# cam.net
KiCad netlist of a schematic drawn in EAGLE
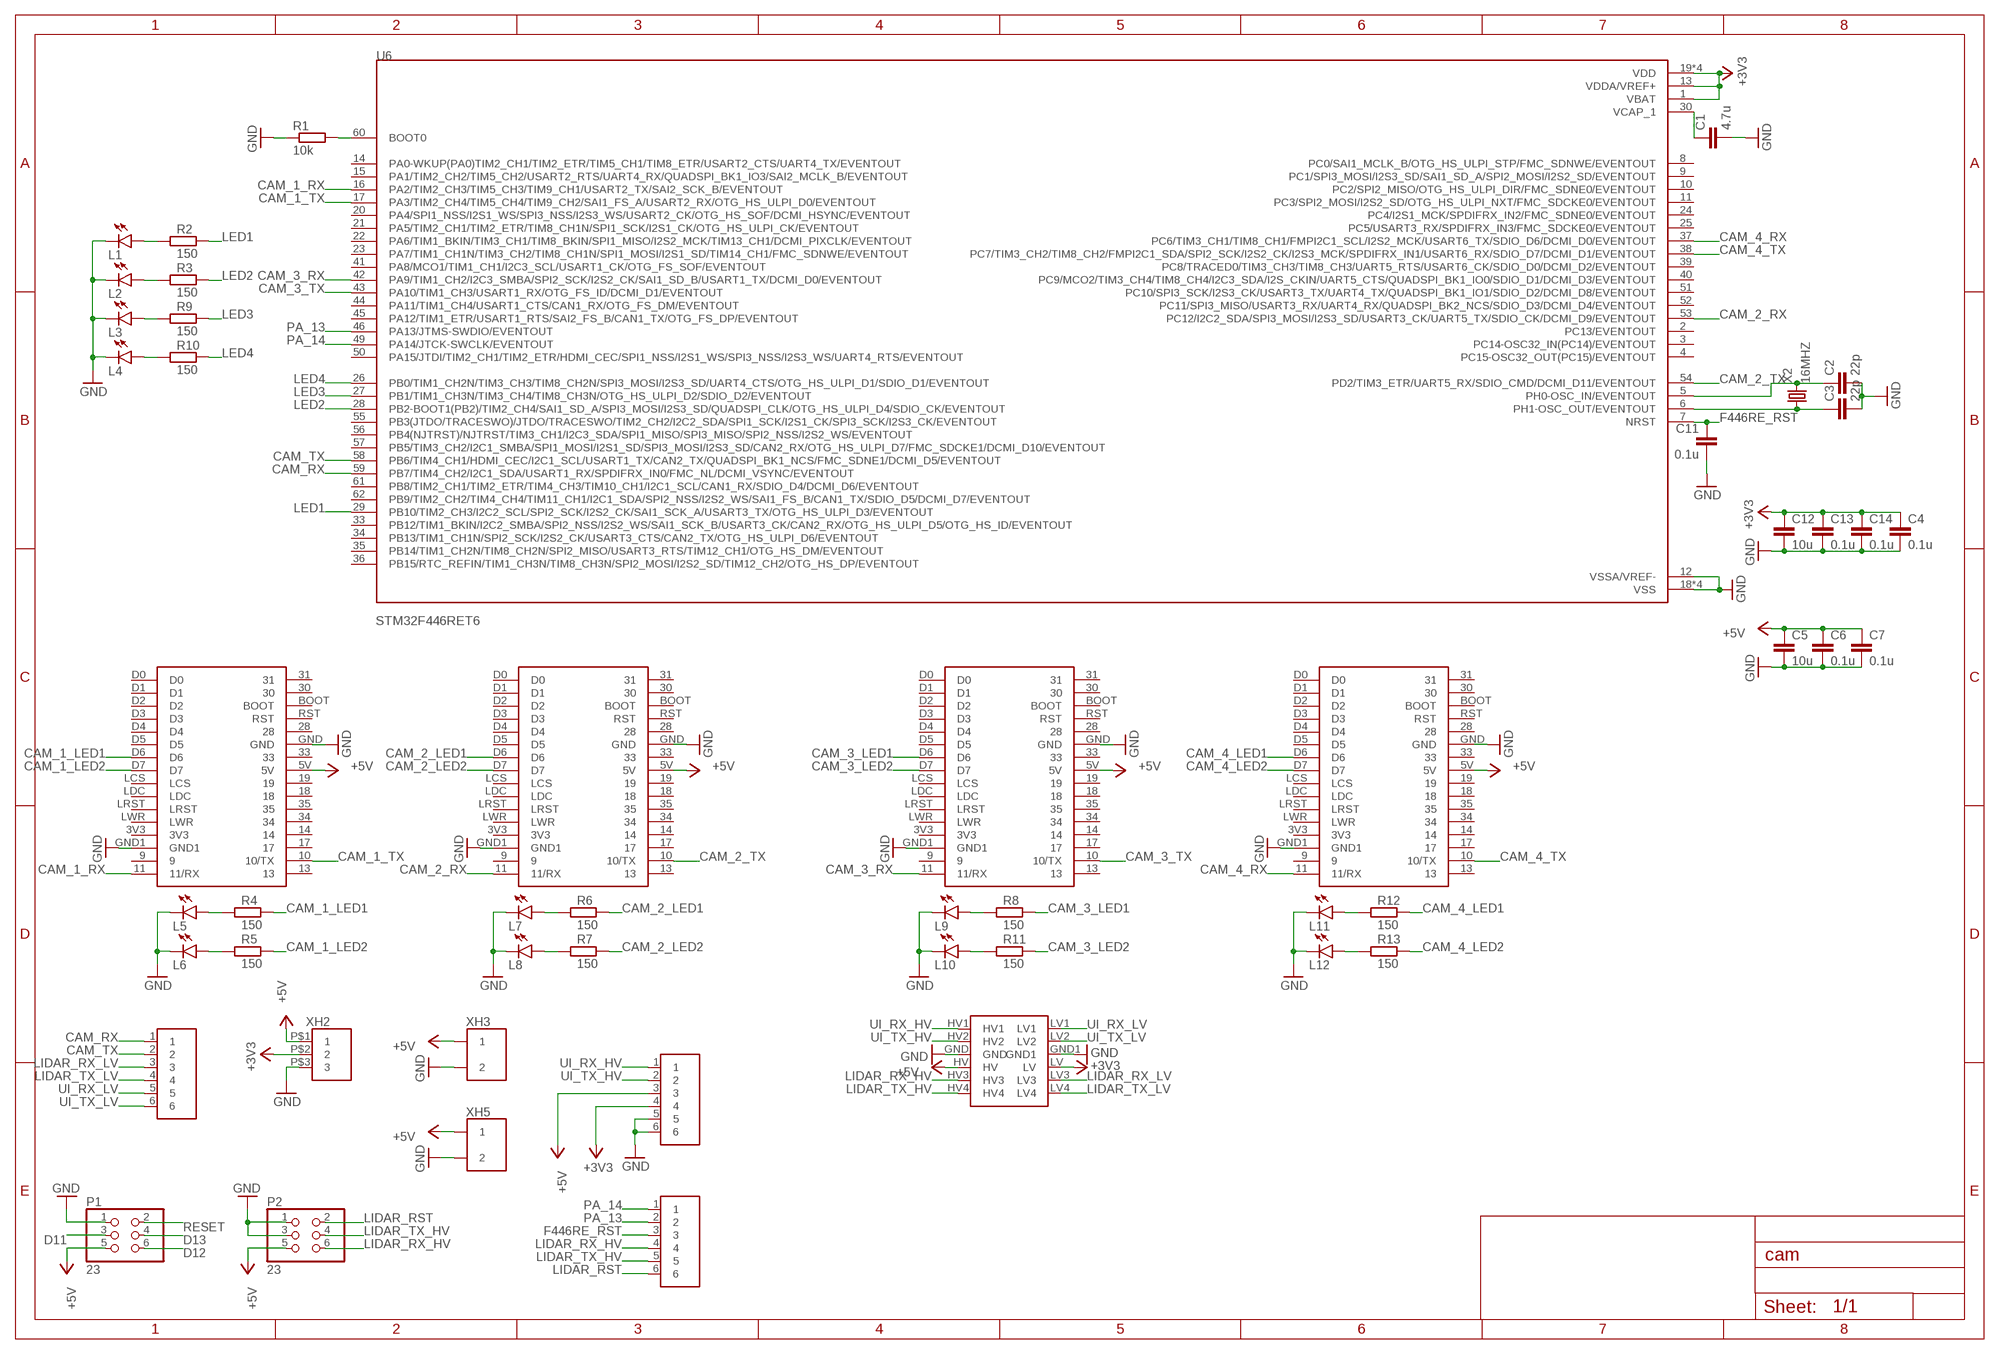
[diagram p0: schematic, sheet 1]

(export (version "E")
  (design (tool "Eeschema 10.0.6"))
  (components
    (comp (ref "C1")
      (value "4.7u")
      (footprint "eagle-import:C0603")
      (libsource (lib "eagle-import") (part "C-EUC0603"))
    )
    (comp (ref "C2")
      (value "22p")
      (footprint "eagle-import:C0603")
      (libsource (lib "eagle-import") (part "C-EUC0603"))
    )
    (comp (ref "C3")
      (value "22p")
      (footprint "eagle-import:C0603")
      (libsource (lib "eagle-import") (part "C-EUC0603"))
    )
    (comp (ref "C4")
      (value "0.1u")
      (footprint "eagle-import:C0603")
      (libsource (lib "eagle-import") (part "C-EUC0603"))
    )
    (comp (ref "C5")
      (value "10u")
      (footprint "eagle-import:C0805")
      (libsource (lib "eagle-import") (part "C-EUC0805"))
    )
    (comp (ref "C6")
      (value "0.1u")
      (footprint "eagle-import:C0603")
      (libsource (lib "eagle-import") (part "C-EUC0603"))
    )
    (comp (ref "C7")
      (value "0.1u")
      (footprint "eagle-import:C0603")
      (libsource (lib "eagle-import") (part "C-EUC0603"))
    )
    (comp (ref "C11")
      (value "0.1u")
      (footprint "eagle-import:C0603")
      (libsource (lib "eagle-import") (part "C-EUC0603"))
    )
    (comp (ref "C12")
      (value "10u")
      (footprint "eagle-import:C0805")
      (libsource (lib "eagle-import") (part "C-EUC0805"))
    )
    (comp (ref "C13")
      (value "0.1u")
      (footprint "eagle-import:C0603")
      (libsource (lib "eagle-import") (part "C-EUC0603"))
    )
    (comp (ref "C14")
      (value "0.1u")
      (footprint "eagle-import:C0603")
      (libsource (lib "eagle-import") (part "C-EUC0603"))
    )
    (comp (ref "L1")
      (value "SML-E12P8WT86")
      (footprint "eagle-import:LED_SML-LXFM0603SIC-TR")
      (libsource (lib "eagle-import") (part "SML-E12P8WT86"))
    )
    (comp (ref "L2")
      (value "SML-E12P8WT86")
      (footprint "eagle-import:LED_SML-LXFM0603SIC-TR")
      (libsource (lib "eagle-import") (part "SML-E12P8WT86"))
    )
    (comp (ref "L3")
      (value "SML-E12P8WT86")
      (footprint "eagle-import:LED_SML-LXFM0603SIC-TR")
      (libsource (lib "eagle-import") (part "SML-E12P8WT86"))
    )
    (comp (ref "L4")
      (value "SML-E12P8WT86")
      (footprint "eagle-import:LED_SML-LXFM0603SIC-TR")
      (libsource (lib "eagle-import") (part "SML-E12P8WT86"))
    )
    (comp (ref "L5")
      (value "SML-E12P8WT86")
      (footprint "eagle-import:LED_SML-LXFM0603SIC-TR")
      (libsource (lib "eagle-import") (part "SML-E12P8WT86"))
    )
    (comp (ref "L6")
      (value "SML-E12P8WT86")
      (footprint "eagle-import:LED_SML-LXFM0603SIC-TR")
      (libsource (lib "eagle-import") (part "SML-E12P8WT86"))
    )
    (comp (ref "L7")
      (value "SML-E12P8WT86")
      (footprint "eagle-import:LED_SML-LXFM0603SIC-TR")
      (libsource (lib "eagle-import") (part "SML-E12P8WT86"))
    )
    (comp (ref "L8")
      (value "SML-E12P8WT86")
      (footprint "eagle-import:LED_SML-LXFM0603SIC-TR")
      (libsource (lib "eagle-import") (part "SML-E12P8WT86"))
    )
    (comp (ref "L9")
      (value "SML-E12P8WT86")
      (footprint "eagle-import:LED_SML-LXFM0603SIC-TR")
      (libsource (lib "eagle-import") (part "SML-E12P8WT86"))
    )
    (comp (ref "L10")
      (value "SML-E12P8WT86")
      (footprint "eagle-import:LED_SML-LXFM0603SIC-TR")
      (libsource (lib "eagle-import") (part "SML-E12P8WT86"))
    )
    (comp (ref "L11")
      (value "SML-E12P8WT86")
      (footprint "eagle-import:LED_SML-LXFM0603SIC-TR")
      (libsource (lib "eagle-import") (part "SML-E12P8WT86"))
    )
    (comp (ref "L12")
      (value "SML-E12P8WT86")
      (footprint "eagle-import:LED_SML-LXFM0603SIC-TR")
      (libsource (lib "eagle-import") (part "SML-E12P8WT86"))
    )
    (comp (ref "P1") (value "23") (footprint "eagle-import:2_3") (libsource (lib "eagle-import") (part "23")))
    (comp (ref "P2") (value "23") (footprint "eagle-import:2_3") (libsource (lib "eagle-import") (part "23")))
    (comp (ref "Q1")
      (value "BSS138")
      (footprint "eagle-import:BSS138")
      (libsource (lib "eagle-import") (part "BSS138"))
    )
    (comp (ref "R1")
      (value "10k")
      (footprint "eagle-import:R0603")
      (libsource (lib "eagle-import") (part "R-EU_R0603"))
    )
    (comp (ref "R2")
      (value "150")
      (footprint "eagle-import:R0603")
      (libsource (lib "eagle-import") (part "R-EU_R0603"))
    )
    (comp (ref "R3")
      (value "150")
      (footprint "eagle-import:R0603")
      (libsource (lib "eagle-import") (part "R-EU_R0603"))
    )
    (comp (ref "R4")
      (value "150")
      (footprint "eagle-import:R0603")
      (libsource (lib "eagle-import") (part "R-EU_R0603"))
    )
    (comp (ref "R5")
      (value "150")
      (footprint "eagle-import:R0603")
      (libsource (lib "eagle-import") (part "R-EU_R0603"))
    )
    (comp (ref "R6")
      (value "150")
      (footprint "eagle-import:R0603")
      (libsource (lib "eagle-import") (part "R-EU_R0603"))
    )
    (comp (ref "R7")
      (value "150")
      (footprint "eagle-import:R0603")
      (libsource (lib "eagle-import") (part "R-EU_R0603"))
    )
    (comp (ref "R8")
      (value "150")
      (footprint "eagle-import:R0603")
      (libsource (lib "eagle-import") (part "R-EU_R0603"))
    )
    (comp (ref "R9")
      (value "150")
      (footprint "eagle-import:R0603")
      (libsource (lib "eagle-import") (part "R-EU_R0603"))
    )
    (comp (ref "R10")
      (value "150")
      (footprint "eagle-import:R0603")
      (libsource (lib "eagle-import") (part "R-EU_R0603"))
    )
    (comp (ref "R11")
      (value "150")
      (footprint "eagle-import:R0603")
      (libsource (lib "eagle-import") (part "R-EU_R0603"))
    )
    (comp (ref "R12")
      (value "150")
      (footprint "eagle-import:R0603")
      (libsource (lib "eagle-import") (part "R-EU_R0603"))
    )
    (comp (ref "R13")
      (value "150")
      (footprint "eagle-import:R0603")
      (libsource (lib "eagle-import") (part "R-EU_R0603"))
    )
    (comp (ref "U1")
      (value "M1N")
      (footprint "eagle-import:M1N")
      (libsource (lib "eagle-import") (part "M1N"))
    )
    (comp (ref "U2")
      (value "M1N")
      (footprint "eagle-import:M1N")
      (libsource (lib "eagle-import") (part "M1N"))
    )
    (comp (ref "U3")
      (value "M1N")
      (footprint "eagle-import:M1N")
      (libsource (lib "eagle-import") (part "M1N"))
    )
    (comp (ref "U4")
      (value "M1N")
      (footprint "eagle-import:M1N")
      (libsource (lib "eagle-import") (part "M1N"))
    )
    (comp (ref "U6")
      (value "STM32F446RET6")
      (footprint "eagle-import:QFP50P1200X1200X160-64N")
      (fields (field (name "MF") "STMicroelectronics"))
      (libsource (lib "eagle-import") (part "STM32F446RET6"))
    )
    (comp (ref "X2")
      (value "16MHZ")
      (footprint "eagle-import:16MHZ")
      (libsource (lib "eagle-import") (part "16MHZ"))
    )
    (comp (ref "XH1") (value "6B") (footprint "eagle-import:6B") (libsource (lib "eagle-import") (part "6B")))
    (comp (ref "XH2") (value "3B") (footprint "eagle-import:3B") (libsource (lib "eagle-import") (part "3B")))
    (comp (ref "XH3") (value "2B") (footprint "eagle-import:2B") (libsource (lib "eagle-import") (part "2B")))
    (comp (ref "XH4") (value "6B") (footprint "eagle-import:6B") (libsource (lib "eagle-import") (part "6B")))
    (comp (ref "XH5") (value "2B") (footprint "eagle-import:2B") (libsource (lib "eagle-import") (part "2B")))
    (comp (ref "XH6") (value "6B") (footprint "eagle-import:6B") (libsource (lib "eagle-import") (part "6B")))
  )
  (nets
    (net (code "1") (name "+3V3") (class "Default")
      (node (ref "C12") (pin "1") (pinfunction "1_1") (pintype "passive"))
      (node (ref "C13") (pin "1") (pinfunction "1_1") (pintype "passive"))
      (node (ref "C14") (pin "1") (pinfunction "1_1") (pintype "passive"))
      (node (ref "C4") (pin "1") (pinfunction "1_1") (pintype "passive"))
      (node (ref "Q1") (pin "LV") (pinfunction "LV_LV") (pintype "bidirectional"))
      (node (ref "U6") (pin "1") (pinfunction "VBAT_1") (pintype "power_in"))
      (node (ref "U6") (pin "13") (pinfunction "VDDA/VREF+_13") (pintype "power_in"))
      (node (ref "U6") (pin "19") (pinfunction "VDD_19") (pintype "power_in"))
      (node (ref "U6") (pin "32") (pinfunction "VDD_32") (pintype "power_in"))
      (node (ref "U6") (pin "48") (pinfunction "VDD_48") (pintype "power_in"))
      (node (ref "U6") (pin "64") (pinfunction "VDD_64") (pintype "power_in"))
      (node (ref "XH2") (pin "P$2") (pinfunction "2_P$2") (pintype "bidirectional"))
      (node (ref "XH4") (pin "4") (pinfunction "4_4") (pintype "bidirectional"))
    )
    (net (code "2") (name "+5V") (class "Default")
      (node (ref "C5") (pin "1") (pinfunction "1_1") (pintype "passive"))
      (node (ref "C6") (pin "1") (pinfunction "1_1") (pintype "passive"))
      (node (ref "C7") (pin "1") (pinfunction "1_1") (pintype "passive"))
      (node (ref "P1") (pin "5") (pinfunction "5_5") (pintype "passive"))
      (node (ref "P2") (pin "5") (pinfunction "5_5") (pintype "passive"))
      (node (ref "Q1") (pin "HV") (pinfunction "HV_HV") (pintype "bidirectional"))
      (node (ref "U1") (pin "5V") (pinfunction "5V_5V") (pintype "bidirectional"))
      (node (ref "U2") (pin "5V") (pinfunction "5V_5V") (pintype "bidirectional"))
      (node (ref "U3") (pin "5V") (pinfunction "5V_5V") (pintype "bidirectional"))
      (node (ref "U4") (pin "5V") (pinfunction "5V_5V") (pintype "bidirectional"))
      (node (ref "XH2") (pin "P$1") (pinfunction "1_P$1") (pintype "bidirectional"))
      (node (ref "XH3") (pin "P$1") (pinfunction "1_P$1") (pintype "bidirectional"))
      (node (ref "XH4") (pin "3") (pinfunction "3_3") (pintype "bidirectional"))
      (node (ref "XH5") (pin "P$1") (pinfunction "1_P$1") (pintype "bidirectional"))
    )
    (net (code "3") (name "/CAM_1_LED1") (class "Default")
      (node (ref "R4") (pin "2") (pinfunction "2_2") (pintype "passive"))
      (node (ref "U1") (pin "D6") (pinfunction "D6_D6") (pintype "bidirectional"))
    )
    (net (code "4") (name "/CAM_1_LED2") (class "Default")
      (node (ref "R5") (pin "2") (pinfunction "2_2") (pintype "passive"))
      (node (ref "U1") (pin "D7") (pinfunction "D7_D7") (pintype "bidirectional"))
    )
    (net (code "5") (name "/CAM_1_RX") (class "Default")
      (node (ref "U1") (pin "11") (pinfunction "11/RX_11") (pintype "bidirectional"))
      (node (ref "U6") (pin "16") (pinfunction "PA2/TIM2_CH3/TIM5_CH3/TIM9_CH1/USART2_TX/SAI2_SCK_B/EVENTOUT_16") (pintype "bidirectional"))
    )
    (net (code "6") (name "/CAM_1_TX") (class "Default")
      (node (ref "U1") (pin "10") (pinfunction "10/TX_10") (pintype "bidirectional"))
      (node (ref "U6") (pin "17") (pinfunction "PA3/TIM2_CH4/TIM5_CH4/TIM9_CH2/SAI1_FS_A/USART2_RX/OTG_HS_ULPI_D0/EVENTOUT_17") (pintype "bidirectional"))
    )
    (net (code "7") (name "/CAM_2_LED1") (class "Default")
      (node (ref "R6") (pin "2") (pinfunction "2_2") (pintype "passive"))
      (node (ref "U2") (pin "D6") (pinfunction "D6_D6") (pintype "bidirectional"))
    )
    (net (code "8") (name "/CAM_2_LED2") (class "Default")
      (node (ref "R7") (pin "2") (pinfunction "2_2") (pintype "passive"))
      (node (ref "U2") (pin "D7") (pinfunction "D7_D7") (pintype "bidirectional"))
    )
    (net (code "9") (name "/CAM_2_RX") (class "Default")
      (node (ref "U2") (pin "11") (pinfunction "11/RX_11") (pintype "bidirectional"))
      (node (ref "U6") (pin "53") (pinfunction "PC12/I2C2_SDA/SPI3_MOSI/I2S3_SD/USART3_CK/UART5_TX/SDIO_CK/DCMI_D9/EVENTOUT_53") (pintype "bidirectional"))
    )
    (net (code "10") (name "/CAM_2_TX") (class "Default")
      (node (ref "U2") (pin "10") (pinfunction "10/TX_10") (pintype "bidirectional"))
      (node (ref "U6") (pin "54") (pinfunction "PD2/TIM3_ETR/UART5_RX/SDIO_CMD/DCMI_D11/EVENTOUT_54") (pintype "bidirectional"))
    )
    (net (code "11") (name "/CAM_3_LED1") (class "Default")
      (node (ref "R8") (pin "2") (pinfunction "2_2") (pintype "passive"))
      (node (ref "U3") (pin "D6") (pinfunction "D6_D6") (pintype "bidirectional"))
    )
    (net (code "12") (name "/CAM_3_LED2") (class "Default")
      (node (ref "R11") (pin "2") (pinfunction "2_2") (pintype "passive"))
      (node (ref "U3") (pin "D7") (pinfunction "D7_D7") (pintype "bidirectional"))
    )
    (net (code "13") (name "/CAM_3_RX") (class "Default")
      (node (ref "U3") (pin "11") (pinfunction "11/RX_11") (pintype "bidirectional"))
      (node (ref "U6") (pin "42") (pinfunction "PA9/TIM1_CH2/I2C3_SMBA/SPI2_SCK/I2S2_CK/SAI1_SD_B/USART1_TX/DCMI_D0/EVENTOUT_42") (pintype "bidirectional"))
    )
    (net (code "14") (name "/CAM_3_TX") (class "Default")
      (node (ref "U3") (pin "10") (pinfunction "10/TX_10") (pintype "bidirectional"))
      (node (ref "U6") (pin "43") (pinfunction "PA10/TIM1_CH3/USART1_RX/OTG_FS_ID/DCMI_D1/EVENTOUT_43") (pintype "bidirectional"))
    )
    (net (code "15") (name "/CAM_4_LED1") (class "Default")
      (node (ref "R12") (pin "2") (pinfunction "2_2") (pintype "passive"))
      (node (ref "U4") (pin "D6") (pinfunction "D6_D6") (pintype "bidirectional"))
    )
    (net (code "16") (name "/CAM_4_LED2") (class "Default")
      (node (ref "R13") (pin "2") (pinfunction "2_2") (pintype "passive"))
      (node (ref "U4") (pin "D7") (pinfunction "D7_D7") (pintype "bidirectional"))
    )
    (net (code "17") (name "/CAM_4_RX") (class "Default")
      (node (ref "U4") (pin "11") (pinfunction "11/RX_11") (pintype "bidirectional"))
      (node (ref "U6") (pin "37") (pinfunction "PC6/TIM3_CH1/TIM8_CH1/FMPI2C1_SCL/I2S2_MCK/USART6_TX/SDIO_D6/DCMI_D0/EVENTOUT_37") (pintype "bidirectional"))
    )
    (net (code "18") (name "/CAM_4_TX") (class "Default")
      (node (ref "U4") (pin "10") (pinfunction "10/TX_10") (pintype "bidirectional"))
      (node (ref "U6") (pin "38") (pinfunction "PC7/TIM3_CH2/TIM8_CH2/FMPI2C1_SDA/SPI2_SCK/I2S2_CK/I2S3_MCK/SPDIFRX_IN1/USART6_RX/SDIO_D7/DCMI_D1/EVENTOUT_38") (pintype "bidirectional"))
    )
    (net (code "19") (name "/CAM_RX") (class "Default")
      (node (ref "U6") (pin "59") (pinfunction "PB7/TIM4_CH2/I2C1_SDA/USART1_RX/SPDIFRX_IN0/FMC_NL/DCMI_VSYNC/EVENTOUT_59") (pintype "bidirectional"))
      (node (ref "XH1") (pin "1") (pinfunction "1_1") (pintype "bidirectional"))
    )
    (net (code "20") (name "/CAM_TX") (class "Default")
      (node (ref "U6") (pin "58") (pinfunction "PB6/TIM4_CH1/HDMI_CEC/I2C1_SCL/USART1_TX/CAN2_TX/QUADSPI_BK1_NCS/FMC_SDNE1/DCMI_D5/EVENTOUT_58") (pintype "bidirectional"))
      (node (ref "XH1") (pin "2") (pinfunction "2_2") (pintype "bidirectional"))
    )
    (net (code "21") (name "/D11") (class "Default")
      (node (ref "P1") (pin "3") (pinfunction "3_3") (pintype "passive"))
    )
    (net (code "22") (name "/D12") (class "Default")
      (node (ref "P1") (pin "6") (pinfunction "6_6") (pintype "passive"))
    )
    (net (code "23") (name "/D13") (class "Default")
      (node (ref "P1") (pin "4") (pinfunction "4_4") (pintype "passive"))
    )
    (net (code "24") (name "/F446RE_RST") (class "Default")
      (node (ref "C11") (pin "1") (pinfunction "1_1") (pintype "passive"))
      (node (ref "U6") (pin "7") (pinfunction "NRST_7") (pintype "bidirectional"))
      (node (ref "XH6") (pin "3") (pinfunction "3_3") (pintype "bidirectional"))
    )
    (net (code "25") (name "/LED1") (class "Default")
      (node (ref "R2") (pin "2") (pinfunction "2_2") (pintype "passive"))
      (node (ref "U6") (pin "29") (pinfunction "PB10/TIM2_CH3/I2C2_SCL/SPI2_SCK/I2S2_CK/SAI1_SCK_A/USART3_TX/OTG_HS_ULPI_D3/EVENTOUT_29") (pintype "bidirectional"))
    )
    (net (code "26") (name "/LED2") (class "Default")
      (node (ref "R3") (pin "2") (pinfunction "2_2") (pintype "passive"))
      (node (ref "U6") (pin "28") (pinfunction "PB2-BOOT1(PB2)/TIM2_CH4/SAI1_SD_A/SPI3_MOSI/I2S3_SD/QUADSPI_CLK/OTG_HS_ULPI_D4/SDIO_CK/EVENTOUT_28") (pintype "bidirectional"))
    )
    (net (code "27") (name "/LED3") (class "Default")
      (node (ref "R9") (pin "2") (pinfunction "2_2") (pintype "passive"))
      (node (ref "U6") (pin "27") (pinfunction "PB1/TIM1_CH3N/TIM3_CH4/TIM8_CH3N/OTG_HS_ULPI_D2/SDIO_D2/EVENTOUT_27") (pintype "bidirectional"))
    )
    (net (code "28") (name "/LED4") (class "Default")
      (node (ref "R10") (pin "2") (pinfunction "2_2") (pintype "passive"))
      (node (ref "U6") (pin "26") (pinfunction "PB0/TIM1_CH2N/TIM3_CH3/TIM8_CH2N/SPI3_MOSI/I2S3_SD/UART4_CTS/OTG_HS_ULPI_D1/SDIO_D1/EVENTOUT_26") (pintype "bidirectional"))
    )
    (net (code "29") (name "/LIDAR_RST") (class "Default")
      (node (ref "P2") (pin "2") (pinfunction "2_2") (pintype "passive"))
      (node (ref "XH6") (pin "6") (pinfunction "6_6") (pintype "bidirectional"))
    )
    (net (code "30") (name "/LIDAR_RX_HV") (class "Default")
      (node (ref "P2") (pin "6") (pinfunction "6_6") (pintype "passive"))
      (node (ref "Q1") (pin "HV3") (pinfunction "HV3_HV3") (pintype "bidirectional"))
      (node (ref "XH6") (pin "4") (pinfunction "4_4") (pintype "bidirectional"))
    )
    (net (code "31") (name "/LIDAR_RX_LV") (class "Default")
      (node (ref "Q1") (pin "LV3") (pinfunction "LV3_LV3") (pintype "bidirectional"))
      (node (ref "XH1") (pin "3") (pinfunction "3_3") (pintype "bidirectional"))
    )
    (net (code "32") (name "/LIDAR_TX_HV") (class "Default")
      (node (ref "P2") (pin "4") (pinfunction "4_4") (pintype "passive"))
      (node (ref "Q1") (pin "HV4") (pinfunction "HV4_HV4") (pintype "bidirectional"))
      (node (ref "XH6") (pin "5") (pinfunction "5_5") (pintype "bidirectional"))
    )
    (net (code "33") (name "/LIDAR_TX_LV") (class "Default")
      (node (ref "Q1") (pin "LV4") (pinfunction "LV4_LV4") (pintype "bidirectional"))
      (node (ref "XH1") (pin "4") (pinfunction "4_4") (pintype "bidirectional"))
    )
    (net (code "34") (name "/PA_13") (class "Default")
      (node (ref "U6") (pin "46") (pinfunction "PA13/JTMS-SWDIO/EVENTOUT_46") (pintype "bidirectional"))
      (node (ref "XH6") (pin "2") (pinfunction "2_2") (pintype "bidirectional"))
    )
    (net (code "35") (name "/PA_14") (class "Default")
      (node (ref "U6") (pin "49") (pinfunction "PA14/JTCK-SWCLK/EVENTOUT_49") (pintype "bidirectional"))
      (node (ref "XH6") (pin "1") (pinfunction "1_1") (pintype "bidirectional"))
    )
    (net (code "36") (name "/RESET") (class "Default")
      (node (ref "P1") (pin "2") (pinfunction "2_2") (pintype "passive"))
    )
    (net (code "37") (name "/UI_RX_HV") (class "Default")
      (node (ref "Q1") (pin "HV1") (pinfunction "HV1_HV1") (pintype "bidirectional"))
      (node (ref "XH4") (pin "1") (pinfunction "1_1") (pintype "bidirectional"))
    )
    (net (code "38") (name "/UI_RX_LV") (class "Default")
      (node (ref "Q1") (pin "LV1") (pinfunction "LV1_LV1") (pintype "bidirectional"))
      (node (ref "XH1") (pin "5") (pinfunction "5_5") (pintype "bidirectional"))
    )
    (net (code "39") (name "/UI_TX_HV") (class "Default")
      (node (ref "Q1") (pin "HV2") (pinfunction "HV2_HV2") (pintype "bidirectional"))
      (node (ref "XH4") (pin "2") (pinfunction "2_2") (pintype "bidirectional"))
    )
    (net (code "40") (name "/UI_TX_LV") (class "Default")
      (node (ref "Q1") (pin "LV2") (pinfunction "LV2_LV2") (pintype "bidirectional"))
      (node (ref "XH1") (pin "6") (pinfunction "6_6") (pintype "bidirectional"))
    )
    (net (code "41") (name "GND") (class "Default")
      (node (ref "C1") (pin "2") (pinfunction "2_2") (pintype "passive"))
      (node (ref "C11") (pin "2") (pinfunction "2_2") (pintype "passive"))
      (node (ref "C12") (pin "2") (pinfunction "2_2") (pintype "passive"))
      (node (ref "C13") (pin "2") (pinfunction "2_2") (pintype "passive"))
      (node (ref "C14") (pin "2") (pinfunction "2_2") (pintype "passive"))
      (node (ref "C2") (pin "2") (pinfunction "2_2") (pintype "passive"))
      (node (ref "C3") (pin "2") (pinfunction "2_2") (pintype "passive"))
      (node (ref "C4") (pin "2") (pinfunction "2_2") (pintype "passive"))
      (node (ref "C5") (pin "2") (pinfunction "2_2") (pintype "passive"))
      (node (ref "C6") (pin "2") (pinfunction "2_2") (pintype "passive"))
      (node (ref "C7") (pin "2") (pinfunction "2_2") (pintype "passive"))
      (node (ref "L1") (pin "C") (pinfunction "C_C") (pintype "passive"))
      (node (ref "L10") (pin "C") (pinfunction "C_C") (pintype "passive"))
      (node (ref "L11") (pin "C") (pinfunction "C_C") (pintype "passive"))
      (node (ref "L12") (pin "C") (pinfunction "C_C") (pintype "passive"))
      (node (ref "L2") (pin "C") (pinfunction "C_C") (pintype "passive"))
      (node (ref "L3") (pin "C") (pinfunction "C_C") (pintype "passive"))
      (node (ref "L4") (pin "C") (pinfunction "C_C") (pintype "passive"))
      (node (ref "L5") (pin "C") (pinfunction "C_C") (pintype "passive"))
      (node (ref "L6") (pin "C") (pinfunction "C_C") (pintype "passive"))
      (node (ref "L7") (pin "C") (pinfunction "C_C") (pintype "passive"))
      (node (ref "L8") (pin "C") (pinfunction "C_C") (pintype "passive"))
      (node (ref "L9") (pin "C") (pinfunction "C_C") (pintype "passive"))
      (node (ref "P1") (pin "1") (pinfunction "1_1") (pintype "passive"))
      (node (ref "P2") (pin "1") (pinfunction "1_1") (pintype "passive"))
      (node (ref "P2") (pin "3") (pinfunction "3_3") (pintype "passive"))
      (node (ref "Q1") (pin "GND") (pinfunction "GND_GND") (pintype "bidirectional"))
      (node (ref "Q1") (pin "GND1") (pinfunction "GND1_GND1") (pintype "bidirectional"))
      (node (ref "R1") (pin "1") (pinfunction "1_1") (pintype "passive"))
      (node (ref "U1") (pin "GND") (pinfunction "GND_GND") (pintype "bidirectional"))
      (node (ref "U1") (pin "GND1") (pinfunction "GND1_GND1") (pintype "bidirectional"))
      (node (ref "U2") (pin "GND") (pinfunction "GND_GND") (pintype "bidirectional"))
      (node (ref "U2") (pin "GND1") (pinfunction "GND1_GND1") (pintype "bidirectional"))
      (node (ref "U3") (pin "GND") (pinfunction "GND_GND") (pintype "bidirectional"))
      (node (ref "U3") (pin "GND1") (pinfunction "GND1_GND1") (pintype "bidirectional"))
      (node (ref "U4") (pin "GND") (pinfunction "GND_GND") (pintype "bidirectional"))
      (node (ref "U4") (pin "GND1") (pinfunction "GND1_GND1") (pintype "bidirectional"))
      (node (ref "U6") (pin "12") (pinfunction "VSSA/VREF-_12") (pintype "power_in"))
      (node (ref "U6") (pin "18") (pinfunction "VSS_18") (pintype "power_in"))
      (node (ref "U6") (pin "31") (pinfunction "VSS_31") (pintype "power_in"))
      (node (ref "U6") (pin "47") (pinfunction "VSS_47") (pintype "power_in"))
      (node (ref "U6") (pin "63") (pinfunction "VSS_63") (pintype "power_in"))
      (node (ref "XH2") (pin "P$3") (pinfunction "3_P$3") (pintype "bidirectional"))
      (node (ref "XH3") (pin "P$2") (pinfunction "2_P$2") (pintype "bidirectional"))
      (node (ref "XH4") (pin "5") (pinfunction "5_5") (pintype "bidirectional"))
      (node (ref "XH4") (pin "6") (pinfunction "6_6") (pintype "bidirectional"))
      (node (ref "XH5") (pin "P$2") (pinfunction "2_P$2") (pintype "bidirectional"))
    )
    (net (code "42") (name "Net-(L1-PadA)") (class "Default")
      (node (ref "L1") (pin "A") (pinfunction "A_A") (pintype "passive"))
      (node (ref "R2") (pin "1") (pinfunction "1_1") (pintype "passive"))
    )
    (net (code "43") (name "Net-(L2-PadA)") (class "Default")
      (node (ref "L2") (pin "A") (pinfunction "A_A") (pintype "passive"))
      (node (ref "R3") (pin "1") (pinfunction "1_1") (pintype "passive"))
    )
    (net (code "44") (name "Net-(L3-PadA)") (class "Default")
      (node (ref "L3") (pin "A") (pinfunction "A_A") (pintype "passive"))
      (node (ref "R9") (pin "1") (pinfunction "1_1") (pintype "passive"))
    )
    (net (code "45") (name "Net-(L4-PadA)") (class "Default")
      (node (ref "L4") (pin "A") (pinfunction "A_A") (pintype "passive"))
      (node (ref "R10") (pin "1") (pinfunction "1_1") (pintype "passive"))
    )
    (net (code "46") (name "Net-(L5-PadA)") (class "Default")
      (node (ref "L5") (pin "A") (pinfunction "A_A") (pintype "passive"))
      (node (ref "R4") (pin "1") (pinfunction "1_1") (pintype "passive"))
    )
    (net (code "47") (name "Net-(L6-PadA)") (class "Default")
      (node (ref "L6") (pin "A") (pinfunction "A_A") (pintype "passive"))
      (node (ref "R5") (pin "1") (pinfunction "1_1") (pintype "passive"))
    )
    (net (code "48") (name "Net-(L7-PadA)") (class "Default")
      (node (ref "L7") (pin "A") (pinfunction "A_A") (pintype "passive"))
      (node (ref "R6") (pin "1") (pinfunction "1_1") (pintype "passive"))
    )
    (net (code "49") (name "Net-(L8-PadA)") (class "Default")
      (node (ref "L8") (pin "A") (pinfunction "A_A") (pintype "passive"))
      (node (ref "R7") (pin "1") (pinfunction "1_1") (pintype "passive"))
    )
    (net (code "50") (name "Net-(L9-PadA)") (class "Default")
      (node (ref "L9") (pin "A") (pinfunction "A_A") (pintype "passive"))
      (node (ref "R8") (pin "1") (pinfunction "1_1") (pintype "passive"))
    )
    (net (code "51") (name "Net-(L10-PadA)") (class "Default")
      (node (ref "L10") (pin "A") (pinfunction "A_A") (pintype "passive"))
      (node (ref "R11") (pin "1") (pinfunction "1_1") (pintype "passive"))
    )
    (net (code "52") (name "Net-(L11-PadA)") (class "Default")
      (node (ref "L11") (pin "A") (pinfunction "A_A") (pintype "passive"))
      (node (ref "R12") (pin "1") (pinfunction "1_1") (pintype "passive"))
    )
    (net (code "53") (name "Net-(L12-PadA)") (class "Default")
      (node (ref "L12") (pin "A") (pinfunction "A_A") (pintype "passive"))
      (node (ref "R13") (pin "1") (pinfunction "1_1") (pintype "passive"))
    )
    (net (code "54") (name "Net-(U6-BOOT0)") (class "Default")
      (node (ref "R1") (pin "2") (pinfunction "2_2") (pintype "passive"))
      (node (ref "U6") (pin "60") (pinfunction "BOOT0_60") (pintype "input"))
    )
    (net (code "55") (name "Net-(U6-PH0-OSC_IN{slash}EVENTOUT)") (class "Default")
      (node (ref "C2") (pin "1") (pinfunction "1_1") (pintype "passive"))
      (node (ref "U6") (pin "5") (pinfunction "PH0-OSC_IN/EVENTOUT_5") (pintype "bidirectional"))
      (node (ref "X2") (pin "P$2") (pinfunction "2_P$2") (pintype "passive"))
    )
    (net (code "56") (name "Net-(U6-PH1-OSC_OUT{slash}EVENTOUT)") (class "Default")
      (node (ref "C3") (pin "1") (pinfunction "1_1") (pintype "passive"))
      (node (ref "U6") (pin "6") (pinfunction "PH1-OSC_OUT/EVENTOUT_6") (pintype "bidirectional"))
      (node (ref "X2") (pin "P$1") (pinfunction "1_P$1") (pintype "passive"))
    )
    (net (code "57") (name "Net-(U6-VCAP_1)") (class "Default")
      (node (ref "C1") (pin "1") (pinfunction "1_1") (pintype "passive"))
      (node (ref "U6") (pin "30") (pinfunction "VCAP_1_30") (pintype "power_in"))
    )
    (net (code "58") (name "unconnected-(U1-Pad3V3)") (class "Default")
      (node (ref "U1") (pin "3V3") (pinfunction "3V3_3V3") (pintype "bidirectional"))
    )
    (net (code "59") (name "unconnected-(U1-Pad9)") (class "Default")
      (node (ref "U1") (pin "9") (pinfunction "9_9") (pintype "bidirectional"))
    )
    (net (code "60") (name "unconnected-(U1-Pad13)") (class "Default")
      (node (ref "U1") (pin "13") (pinfunction "13_13") (pintype "bidirectional"))
    )
    (net (code "61") (name "unconnected-(U1-Pad14)") (class "Default")
      (node (ref "U1") (pin "14") (pinfunction "14_14") (pintype "bidirectional"))
    )
    (net (code "62") (name "unconnected-(U1-Pad17)") (class "Default")
      (node (ref "U1") (pin "17") (pinfunction "17_17") (pintype "bidirectional"))
    )
    (net (code "63") (name "unconnected-(U1-Pad18)") (class "Default")
      (node (ref "U1") (pin "18") (pinfunction "18_18") (pintype "bidirectional"))
    )
    (net (code "64") (name "unconnected-(U1-Pad19)") (class "Default")
      (node (ref "U1") (pin "19") (pinfunction "19_19") (pintype "bidirectional"))
    )
    (net (code "65") (name "unconnected-(U1-Pad28)") (class "Default")
      (node (ref "U1") (pin "28") (pinfunction "28_28") (pintype "bidirectional"))
    )
    (net (code "66") (name "unconnected-(U1-Pad30)") (class "Default")
      (node (ref "U1") (pin "30") (pinfunction "30_30") (pintype "bidirectional"))
    )
    (net (code "67") (name "unconnected-(U1-Pad31)") (class "Default")
      (node (ref "U1") (pin "31") (pinfunction "31_31") (pintype "bidirectional"))
    )
    (net (code "68") (name "unconnected-(U1-Pad33)") (class "Default")
      (node (ref "U1") (pin "33") (pinfunction "33_33") (pintype "bidirectional"))
    )
    (net (code "69") (name "unconnected-(U1-Pad34)") (class "Default")
      (node (ref "U1") (pin "34") (pinfunction "34_34") (pintype "bidirectional"))
    )
    (net (code "70") (name "unconnected-(U1-Pad35)") (class "Default")
      (node (ref "U1") (pin "35") (pinfunction "35_35") (pintype "bidirectional"))
    )
    (net (code "71") (name "unconnected-(U1-PadBOOT)") (class "Default")
      (node (ref "U1") (pin "BOOT") (pinfunction "BOOT_BOOT") (pintype "bidirectional"))
    )
    (net (code "72") (name "unconnected-(U1-PadD0)") (class "Default")
      (node (ref "U1") (pin "D0") (pinfunction "D0_D0") (pintype "bidirectional"))
    )
    (net (code "73") (name "unconnected-(U1-PadD1)") (class "Default")
      (node (ref "U1") (pin "D1") (pinfunction "D1_D1") (pintype "bidirectional"))
    )
    (net (code "74") (name "unconnected-(U1-PadD2)") (class "Default")
      (node (ref "U1") (pin "D2") (pinfunction "D2_D2") (pintype "bidirectional"))
    )
    (net (code "75") (name "unconnected-(U1-PadD3)") (class "Default")
      (node (ref "U1") (pin "D3") (pinfunction "D3_D3") (pintype "bidirectional"))
    )
    (net (code "76") (name "unconnected-(U1-PadD4)") (class "Default")
      (node (ref "U1") (pin "D4") (pinfunction "D4_D4") (pintype "bidirectional"))
    )
    (net (code "77") (name "unconnected-(U1-PadD5)") (class "Default")
      (node (ref "U1") (pin "D5") (pinfunction "D5_D5") (pintype "bidirectional"))
    )
    (net (code "78") (name "unconnected-(U1-PadLCS)") (class "Default")
      (node (ref "U1") (pin "LCS") (pinfunction "LCS_LCS") (pintype "bidirectional"))
    )
    (net (code "79") (name "unconnected-(U1-PadLDC)") (class "Default")
      (node (ref "U1") (pin "LDC") (pinfunction "LDC_LDC") (pintype "bidirectional"))
    )
    (net (code "80") (name "unconnected-(U1-PadLRST)") (class "Default")
      (node (ref "U1") (pin "LRST") (pinfunction "LRST_LRST") (pintype "bidirectional"))
    )
    (net (code "81") (name "unconnected-(U1-PadLWR)") (class "Default")
      (node (ref "U1") (pin "LWR") (pinfunction "LWR_LWR") (pintype "bidirectional"))
    )
    (net (code "82") (name "unconnected-(U1-PadRST)") (class "Default")
      (node (ref "U1") (pin "RST") (pinfunction "RST_RST") (pintype "bidirectional"))
    )
    (net (code "83") (name "unconnected-(U2-Pad3V3)") (class "Default")
      (node (ref "U2") (pin "3V3") (pinfunction "3V3_3V3") (pintype "bidirectional"))
    )
    (net (code "84") (name "unconnected-(U2-Pad9)") (class "Default")
      (node (ref "U2") (pin "9") (pinfunction "9_9") (pintype "bidirectional"))
    )
    (net (code "85") (name "unconnected-(U2-Pad13)") (class "Default")
      (node (ref "U2") (pin "13") (pinfunction "13_13") (pintype "bidirectional"))
    )
    (net (code "86") (name "unconnected-(U2-Pad14)") (class "Default")
      (node (ref "U2") (pin "14") (pinfunction "14_14") (pintype "bidirectional"))
    )
    (net (code "87") (name "unconnected-(U2-Pad17)") (class "Default")
      (node (ref "U2") (pin "17") (pinfunction "17_17") (pintype "bidirectional"))
    )
    (net (code "88") (name "unconnected-(U2-Pad18)") (class "Default")
      (node (ref "U2") (pin "18") (pinfunction "18_18") (pintype "bidirectional"))
    )
    (net (code "89") (name "unconnected-(U2-Pad19)") (class "Default")
      (node (ref "U2") (pin "19") (pinfunction "19_19") (pintype "bidirectional"))
    )
    (net (code "90") (name "unconnected-(U2-Pad28)") (class "Default")
      (node (ref "U2") (pin "28") (pinfunction "28_28") (pintype "bidirectional"))
    )
    (net (code "91") (name "unconnected-(U2-Pad30)") (class "Default")
      (node (ref "U2") (pin "30") (pinfunction "30_30") (pintype "bidirectional"))
    )
    (net (code "92") (name "unconnected-(U2-Pad31)") (class "Default")
      (node (ref "U2") (pin "31") (pinfunction "31_31") (pintype "bidirectional"))
    )
    (net (code "93") (name "unconnected-(U2-Pad33)") (class "Default")
      (node (ref "U2") (pin "33") (pinfunction "33_33") (pintype "bidirectional"))
    )
    (net (code "94") (name "unconnected-(U2-Pad34)") (class "Default")
      (node (ref "U2") (pin "34") (pinfunction "34_34") (pintype "bidirectional"))
    )
    (net (code "95") (name "unconnected-(U2-Pad35)") (class "Default")
      (node (ref "U2") (pin "35") (pinfunction "35_35") (pintype "bidirectional"))
    )
    (net (code "96") (name "unconnected-(U2-PadBOOT)") (class "Default")
      (node (ref "U2") (pin "BOOT") (pinfunction "BOOT_BOOT") (pintype "bidirectional"))
    )
    (net (code "97") (name "unconnected-(U2-PadD0)") (class "Default")
      (node (ref "U2") (pin "D0") (pinfunction "D0_D0") (pintype "bidirectional"))
    )
    (net (code "98") (name "unconnected-(U2-PadD1)") (class "Default")
      (node (ref "U2") (pin "D1") (pinfunction "D1_D1") (pintype "bidirectional"))
    )
    (net (code "99") (name "unconnected-(U2-PadD2)") (class "Default")
      (node (ref "U2") (pin "D2") (pinfunction "D2_D2") (pintype "bidirectional"))
    )
    (net (code "100") (name "unconnected-(U2-PadD3)") (class "Default")
      (node (ref "U2") (pin "D3") (pinfunction "D3_D3") (pintype "bidirectional"))
    )
    (net (code "101") (name "unconnected-(U2-PadD4)") (class "Default")
      (node (ref "U2") (pin "D4") (pinfunction "D4_D4") (pintype "bidirectional"))
    )
    (net (code "102") (name "unconnected-(U2-PadD5)") (class "Default")
      (node (ref "U2") (pin "D5") (pinfunction "D5_D5") (pintype "bidirectional"))
    )
    (net (code "103") (name "unconnected-(U2-PadLCS)") (class "Default")
      (node (ref "U2") (pin "LCS") (pinfunction "LCS_LCS") (pintype "bidirectional"))
    )
    (net (code "104") (name "unconnected-(U2-PadLDC)") (class "Default")
      (node (ref "U2") (pin "LDC") (pinfunction "LDC_LDC") (pintype "bidirectional"))
    )
    (net (code "105") (name "unconnected-(U2-PadLRST)") (class "Default")
      (node (ref "U2") (pin "LRST") (pinfunction "LRST_LRST") (pintype "bidirectional"))
    )
    (net (code "106") (name "unconnected-(U2-PadLWR)") (class "Default")
      (node (ref "U2") (pin "LWR") (pinfunction "LWR_LWR") (pintype "bidirectional"))
    )
    (net (code "107") (name "unconnected-(U2-PadRST)") (class "Default")
      (node (ref "U2") (pin "RST") (pinfunction "RST_RST") (pintype "bidirectional"))
    )
    (net (code "108") (name "unconnected-(U3-Pad3V3)") (class "Default")
      (node (ref "U3") (pin "3V3") (pinfunction "3V3_3V3") (pintype "bidirectional"))
    )
    (net (code "109") (name "unconnected-(U3-Pad9)") (class "Default")
      (node (ref "U3") (pin "9") (pinfunction "9_9") (pintype "bidirectional"))
    )
    (net (code "110") (name "unconnected-(U3-Pad13)") (class "Default")
      (node (ref "U3") (pin "13") (pinfunction "13_13") (pintype "bidirectional"))
    )
    (net (code "111") (name "unconnected-(U3-Pad14)") (class "Default")
      (node (ref "U3") (pin "14") (pinfunction "14_14") (pintype "bidirectional"))
    )
    (net (code "112") (name "unconnected-(U3-Pad17)") (class "Default")
      (node (ref "U3") (pin "17") (pinfunction "17_17") (pintype "bidirectional"))
    )
    (net (code "113") (name "unconnected-(U3-Pad18)") (class "Default")
      (node (ref "U3") (pin "18") (pinfunction "18_18") (pintype "bidirectional"))
    )
    (net (code "114") (name "unconnected-(U3-Pad19)") (class "Default")
      (node (ref "U3") (pin "19") (pinfunction "19_19") (pintype "bidirectional"))
    )
    (net (code "115") (name "unconnected-(U3-Pad28)") (class "Default")
      (node (ref "U3") (pin "28") (pinfunction "28_28") (pintype "bidirectional"))
    )
    (net (code "116") (name "unconnected-(U3-Pad30)") (class "Default")
      (node (ref "U3") (pin "30") (pinfunction "30_30") (pintype "bidirectional"))
    )
    (net (code "117") (name "unconnected-(U3-Pad31)") (class "Default")
      (node (ref "U3") (pin "31") (pinfunction "31_31") (pintype "bidirectional"))
    )
    (net (code "118") (name "unconnected-(U3-Pad33)") (class "Default")
      (node (ref "U3") (pin "33") (pinfunction "33_33") (pintype "bidirectional"))
    )
    (net (code "119") (name "unconnected-(U3-Pad34)") (class "Default")
      (node (ref "U3") (pin "34") (pinfunction "34_34") (pintype "bidirectional"))
    )
    (net (code "120") (name "unconnected-(U3-Pad35)") (class "Default")
      (node (ref "U3") (pin "35") (pinfunction "35_35") (pintype "bidirectional"))
    )
    (net (code "121") (name "unconnected-(U3-PadBOOT)") (class "Default")
      (node (ref "U3") (pin "BOOT") (pinfunction "BOOT_BOOT") (pintype "bidirectional"))
    )
    (net (code "122") (name "unconnected-(U3-PadD0)") (class "Default")
      (node (ref "U3") (pin "D0") (pinfunction "D0_D0") (pintype "bidirectional"))
    )
    (net (code "123") (name "unconnected-(U3-PadD1)") (class "Default")
      (node (ref "U3") (pin "D1") (pinfunction "D1_D1") (pintype "bidirectional"))
    )
    (net (code "124") (name "unconnected-(U3-PadD2)") (class "Default")
      (node (ref "U3") (pin "D2") (pinfunction "D2_D2") (pintype "bidirectional"))
    )
    (net (code "125") (name "unconnected-(U3-PadD3)") (class "Default")
      (node (ref "U3") (pin "D3") (pinfunction "D3_D3") (pintype "bidirectional"))
    )
    (net (code "126") (name "unconnected-(U3-PadD4)") (class "Default")
      (node (ref "U3") (pin "D4") (pinfunction "D4_D4") (pintype "bidirectional"))
    )
    (net (code "127") (name "unconnected-(U3-PadD5)") (class "Default")
      (node (ref "U3") (pin "D5") (pinfunction "D5_D5") (pintype "bidirectional"))
    )
    (net (code "128") (name "unconnected-(U3-PadLCS)") (class "Default")
      (node (ref "U3") (pin "LCS") (pinfunction "LCS_LCS") (pintype "bidirectional"))
    )
    (net (code "129") (name "unconnected-(U3-PadLDC)") (class "Default")
      (node (ref "U3") (pin "LDC") (pinfunction "LDC_LDC") (pintype "bidirectional"))
    )
    (net (code "130") (name "unconnected-(U3-PadLRST)") (class "Default")
      (node (ref "U3") (pin "LRST") (pinfunction "LRST_LRST") (pintype "bidirectional"))
    )
    (net (code "131") (name "unconnected-(U3-PadLWR)") (class "Default")
      (node (ref "U3") (pin "LWR") (pinfunction "LWR_LWR") (pintype "bidirectional"))
    )
    (net (code "132") (name "unconnected-(U3-PadRST)") (class "Default")
      (node (ref "U3") (pin "RST") (pinfunction "RST_RST") (pintype "bidirectional"))
    )
    (net (code "133") (name "unconnected-(U4-Pad3V3)") (class "Default")
      (node (ref "U4") (pin "3V3") (pinfunction "3V3_3V3") (pintype "bidirectional"))
    )
    (net (code "134") (name "unconnected-(U4-Pad9)") (class "Default")
      (node (ref "U4") (pin "9") (pinfunction "9_9") (pintype "bidirectional"))
    )
    (net (code "135") (name "unconnected-(U4-Pad13)") (class "Default")
      (node (ref "U4") (pin "13") (pinfunction "13_13") (pintype "bidirectional"))
    )
    (net (code "136") (name "unconnected-(U4-Pad14)") (class "Default")
      (node (ref "U4") (pin "14") (pinfunction "14_14") (pintype "bidirectional"))
    )
    (net (code "137") (name "unconnected-(U4-Pad17)") (class "Default")
      (node (ref "U4") (pin "17") (pinfunction "17_17") (pintype "bidirectional"))
    )
    (net (code "138") (name "unconnected-(U4-Pad18)") (class "Default")
      (node (ref "U4") (pin "18") (pinfunction "18_18") (pintype "bidirectional"))
    )
    (net (code "139") (name "unconnected-(U4-Pad19)") (class "Default")
      (node (ref "U4") (pin "19") (pinfunction "19_19") (pintype "bidirectional"))
    )
    (net (code "140") (name "unconnected-(U4-Pad28)") (class "Default")
      (node (ref "U4") (pin "28") (pinfunction "28_28") (pintype "bidirectional"))
    )
    (net (code "141") (name "unconnected-(U4-Pad30)") (class "Default")
      (node (ref "U4") (pin "30") (pinfunction "30_30") (pintype "bidirectional"))
    )
    (net (code "142") (name "unconnected-(U4-Pad31)") (class "Default")
      (node (ref "U4") (pin "31") (pinfunction "31_31") (pintype "bidirectional"))
    )
    (net (code "143") (name "unconnected-(U4-Pad33)") (class "Default")
      (node (ref "U4") (pin "33") (pinfunction "33_33") (pintype "bidirectional"))
    )
    (net (code "144") (name "unconnected-(U4-Pad34)") (class "Default")
      (node (ref "U4") (pin "34") (pinfunction "34_34") (pintype "bidirectional"))
    )
    (net (code "145") (name "unconnected-(U4-Pad35)") (class "Default")
      (node (ref "U4") (pin "35") (pinfunction "35_35") (pintype "bidirectional"))
    )
    (net (code "146") (name "unconnected-(U4-PadBOOT)") (class "Default")
      (node (ref "U4") (pin "BOOT") (pinfunction "BOOT_BOOT") (pintype "bidirectional"))
    )
    (net (code "147") (name "unconnected-(U4-PadD0)") (class "Default")
      (node (ref "U4") (pin "D0") (pinfunction "D0_D0") (pintype "bidirectional"))
    )
    (net (code "148") (name "unconnected-(U4-PadD1)") (class "Default")
      (node (ref "U4") (pin "D1") (pinfunction "D1_D1") (pintype "bidirectional"))
    )
    (net (code "149") (name "unconnected-(U4-PadD2)") (class "Default")
      (node (ref "U4") (pin "D2") (pinfunction "D2_D2") (pintype "bidirectional"))
    )
    (net (code "150") (name "unconnected-(U4-PadD3)") (class "Default")
      (node (ref "U4") (pin "D3") (pinfunction "D3_D3") (pintype "bidirectional"))
    )
    (net (code "151") (name "unconnected-(U4-PadD4)") (class "Default")
      (node (ref "U4") (pin "D4") (pinfunction "D4_D4") (pintype "bidirectional"))
    )
    (net (code "152") (name "unconnected-(U4-PadD5)") (class "Default")
      (node (ref "U4") (pin "D5") (pinfunction "D5_D5") (pintype "bidirectional"))
    )
    (net (code "153") (name "unconnected-(U4-PadLCS)") (class "Default")
      (node (ref "U4") (pin "LCS") (pinfunction "LCS_LCS") (pintype "bidirectional"))
    )
    (net (code "154") (name "unconnected-(U4-PadLDC)") (class "Default")
      (node (ref "U4") (pin "LDC") (pinfunction "LDC_LDC") (pintype "bidirectional"))
    )
    (net (code "155") (name "unconnected-(U4-PadLRST)") (class "Default")
      (node (ref "U4") (pin "LRST") (pinfunction "LRST_LRST") (pintype "bidirectional"))
    )
    (net (code "156") (name "unconnected-(U4-PadLWR)") (class "Default")
      (node (ref "U4") (pin "LWR") (pinfunction "LWR_LWR") (pintype "bidirectional"))
    )
    (net (code "157") (name "unconnected-(U4-PadRST)") (class "Default")
      (node (ref "U4") (pin "RST") (pinfunction "RST_RST") (pintype "bidirectional"))
    )
    (net (code "158") (name "unconnected-(U6-PA0-WKUP(PA0)TIM2_CH1{slash}TIM2_ETR{slash}TIM5_CH1{slash}TIM8_ETR{slash}USART2_CTS{slash}UART4_TX{slash}EVENTOUT-Pad14)") (class "Default")
      (node (ref "U6") (pin "14") (pinfunction "PA0-WKUP(PA0)TIM2_CH1/TIM2_ETR/TIM5_CH1/TIM8_ETR/USART2_CTS/UART4_TX/EVENTOUT_14") (pintype "bidirectional"))
    )
    (net (code "159") (name "unconnected-(U6-PA1{slash}TIM2_CH2{slash}TIM5_CH2{slash}USART2_RTS{slash}UART4_RX{slash}QUADSPI_BK1_IO3{slash}SAI2_MCLK_B{slash}EVENTOUT-Pad15)") (class "Default")
      (node (ref "U6") (pin "15") (pinfunction "PA1/TIM2_CH2/TIM5_CH2/USART2_RTS/UART4_RX/QUADSPI_BK1_IO3/SAI2_MCLK_B/EVENTOUT_15") (pintype "bidirectional"))
    )
    (net (code "160") (name "unconnected-(U6-PA4{slash}SPI1_NSS{slash}I2S1_WS{slash}SPI3_NSS{slash}I2S3_WS{slash}USART2_CK{slash}OTG_HS_SOF{slash}DCMI_HSYNC{slash}EVENTOUT-Pad20)") (class "Default")
      (node (ref "U6") (pin "20") (pinfunction "PA4/SPI1_NSS/I2S1_WS/SPI3_NSS/I2S3_WS/USART2_CK/OTG_HS_SOF/DCMI_HSYNC/EVENTOUT_20") (pintype "bidirectional"))
    )
    (net (code "161") (name "unconnected-(U6-PA5{slash}TIM2_CH1{slash}TIM2_ETR{slash}TIM8_CH1N{slash}SPI1_SCK{slash}I2S1_CK{slash}OTG_HS_ULPI_CK{slash}EVENTOUT-Pad21)") (class "Default")
      (node (ref "U6") (pin "21") (pinfunction "PA5/TIM2_CH1/TIM2_ETR/TIM8_CH1N/SPI1_SCK/I2S1_CK/OTG_HS_ULPI_CK/EVENTOUT_21") (pintype "bidirectional"))
    )
    (net (code "162") (name "unconnected-(U6-PA6{slash}TIM1_BKIN{slash}TIM3_CH1{slash}TIM8_BKIN{slash}SPI1_MISO{slash}I2S2_MCK{slash}TIM13_CH1{slash}DCMI_PIXCLK{slash}EVENTOUT-Pad22)") (class "Default")
      (node (ref "U6") (pin "22") (pinfunction "PA6/TIM1_BKIN/TIM3_CH1/TIM8_BKIN/SPI1_MISO/I2S2_MCK/TIM13_CH1/DCMI_PIXCLK/EVENTOUT_22") (pintype "bidirectional"))
    )
    (net (code "163") (name "unconnected-(U6-PA7{slash}TIM1_CH1N{slash}TIM3_CH2{slash}TIM8_CH1N{slash}SPI1_MOSI{slash}I2S1_SD{slash}TIM14_CH1{slash}FMC_SDNWE{slash}EVENTOUT-Pad23)") (class "Default")
      (node (ref "U6") (pin "23") (pinfunction "PA7/TIM1_CH1N/TIM3_CH2/TIM8_CH1N/SPI1_MOSI/I2S1_SD/TIM14_CH1/FMC_SDNWE/EVENTOUT_23") (pintype "bidirectional"))
    )
    (net (code "164") (name "unconnected-(U6-PA8{slash}MCO1{slash}TIM1_CH1{slash}I2C3_SCL{slash}USART1_CK{slash}OTG_FS_SOF{slash}EVENTOUT-Pad41)") (class "Default")
      (node (ref "U6") (pin "41") (pinfunction "PA8/MCO1/TIM1_CH1/I2C3_SCL/USART1_CK/OTG_FS_SOF/EVENTOUT_41") (pintype "bidirectional"))
    )
    (net (code "165") (name "unconnected-(U6-PA11{slash}TIM1_CH4{slash}USART1_CTS{slash}CAN1_RX{slash}OTG_FS_DM{slash}EVENTOUT-Pad44)") (class "Default")
      (node (ref "U6") (pin "44") (pinfunction "PA11/TIM1_CH4/USART1_CTS/CAN1_RX/OTG_FS_DM/EVENTOUT_44") (pintype "bidirectional"))
    )
    (net (code "166") (name "unconnected-(U6-PA12{slash}TIM1_ETR{slash}USART1_RTS{slash}SAI2_FS_B{slash}CAN1_TX{slash}OTG_FS_DP{slash}EVENTOUT-Pad45)") (class "Default")
      (node (ref "U6") (pin "45") (pinfunction "PA12/TIM1_ETR/USART1_RTS/SAI2_FS_B/CAN1_TX/OTG_FS_DP/EVENTOUT_45") (pintype "bidirectional"))
    )
    (net (code "167") (name "unconnected-(U6-PA15{slash}JTDI{slash}TIM2_CH1{slash}TIM2_ETR{slash}HDMI_CEC{slash}SPI1_NSS{slash}I2S1_WS{slash}SPI3_NSS{slash}I2S3_WS{slash}UART4_RTS{slash}EVENTOUT-Pad50)") (class "Default")
      (node (ref "U6") (pin "50") (pinfunction "PA15/JTDI/TIM2_CH1/TIM2_ETR/HDMI_CEC/SPI1_NSS/I2S1_WS/SPI3_NSS/I2S3_WS/UART4_RTS/EVENTOUT_50") (pintype "bidirectional"))
    )
    (net (code "168") (name "unconnected-(U6-PB3(JTDO{slash}TRACESWO){slash}JTDO{slash}TRACESWO{slash}TIM2_CH2{slash}I2C2_SDA{slash}SPI1_SCK{slash}I2S1_CK{slash}SPI3_SCK{slash}I2S3_CK{slash}EVENTOUT-Pad55)") (class "Default")
      (node (ref "U6") (pin "55") (pinfunction "PB3(JTDO/TRACESWO)/JTDO/TRACESWO/TIM2_CH2/I2C2_SDA/SPI1_SCK/I2S1_CK/SPI3_SCK/I2S3_CK/EVENTOUT_55") (pintype "bidirectional"))
    )
    (net (code "169") (name "unconnected-(U6-PB4(NJTRST){slash}NJTRST{slash}TIM3_CH1{slash}I2C3_SDA{slash}SPI1_MISO{slash}SPI3_MISO{slash}SPI2_NSS{slash}I2S2_WS{slash}EVENTOUT-Pad56)") (class "Default")
      (node (ref "U6") (pin "56") (pinfunction "PB4(NJTRST)/NJTRST/TIM3_CH1/I2C3_SDA/SPI1_MISO/SPI3_MISO/SPI2_NSS/I2S2_WS/EVENTOUT_56") (pintype "bidirectional"))
    )
    (net (code "170") (name "unconnected-(U6-PB5{slash}TIM3_CH2{slash}I2C1_SMBA{slash}SPI1_MOSI{slash}I2S1_SD{slash}SPI3_MOSI{slash}I2S3_SD{slash}CAN2_RX{slash}OTG_HS_ULPI_D7{slash}FMC_SDCKE1{slash}DCMI_D10{slash}EVENTOUT-Pad57)") (class "Default")
      (node (ref "U6") (pin "57") (pinfunction "PB5/TIM3_CH2/I2C1_SMBA/SPI1_MOSI/I2S1_SD/SPI3_MOSI/I2S3_SD/CAN2_RX/OTG_HS_ULPI_D7/FMC_SDCKE1/DCMI_D10/EVENTOUT_57") (pintype "bidirectional"))
    )
    (net (code "171") (name "unconnected-(U6-PB8{slash}TIM2_CH1{slash}TIM2_ETR{slash}TIM4_CH3{slash}TIM10_CH1{slash}I2C1_SCL{slash}CAN1_RX{slash}SDIO_D4{slash}DCMI_D6{slash}EVENTOUT-Pad61)") (class "Default")
      (node (ref "U6") (pin "61") (pinfunction "PB8/TIM2_CH1/TIM2_ETR/TIM4_CH3/TIM10_CH1/I2C1_SCL/CAN1_RX/SDIO_D4/DCMI_D6/EVENTOUT_61") (pintype "bidirectional"))
    )
    (net (code "172") (name "unconnected-(U6-PB9{slash}TIM2_CH2{slash}TIM4_CH4{slash}TIM11_CH1{slash}I2C1_SDA{slash}SPI2_NSS{slash}I2S2_WS{slash}SAI1_FS_B{slash}CAN1_TX{slash}SDIO_D5{slash}DCMI_D7{slash}EVENTOUT-Pad62)") (class "Default")
      (node (ref "U6") (pin "62") (pinfunction "PB9/TIM2_CH2/TIM4_CH4/TIM11_CH1/I2C1_SDA/SPI2_NSS/I2S2_WS/SAI1_FS_B/CAN1_TX/SDIO_D5/DCMI_D7/EVENTOUT_62") (pintype "bidirectional"))
    )
    (net (code "173") (name "unconnected-(U6-PB12{slash}TIM1_BKIN{slash}I2C2_SMBA{slash}SPI2_NSS{slash}I2S2_WS{slash}SAI1_SCK_B{slash}USART3_CK{slash}CAN2_RX{slash}OTG_HS_ULPI_D5{slash}OTG_HS_ID{slash}EVENTOUT-Pad33)") (class "Default")
      (node (ref "U6") (pin "33") (pinfunction "PB12/TIM1_BKIN/I2C2_SMBA/SPI2_NSS/I2S2_WS/SAI1_SCK_B/USART3_CK/CAN2_RX/OTG_HS_ULPI_D5/OTG_HS_ID/EVENTOUT_33") (pintype "bidirectional"))
    )
    (net (code "174") (name "unconnected-(U6-PB13{slash}TIM1_CH1N{slash}SPI2_SCK{slash}I2S2_CK{slash}USART3_CTS{slash}CAN2_TX{slash}OTG_HS_ULPI_D6{slash}EVENTOUT-Pad34)") (class "Default")
      (node (ref "U6") (pin "34") (pinfunction "PB13/TIM1_CH1N/SPI2_SCK/I2S2_CK/USART3_CTS/CAN2_TX/OTG_HS_ULPI_D6/EVENTOUT_34") (pintype "bidirectional"))
    )
    (net (code "175") (name "unconnected-(U6-PB14{slash}TIM1_CH2N{slash}TIM8_CH2N{slash}SPI2_MISO{slash}USART3_RTS{slash}TIM12_CH1{slash}OTG_HS_DM{slash}EVENTOUT-Pad35)") (class "Default")
      (node (ref "U6") (pin "35") (pinfunction "PB14/TIM1_CH2N/TIM8_CH2N/SPI2_MISO/USART3_RTS/TIM12_CH1/OTG_HS_DM/EVENTOUT_35") (pintype "bidirectional"))
    )
    (net (code "176") (name "unconnected-(U6-PB15{slash}RTC_REFIN{slash}TIM1_CH3N{slash}TIM8_CH3N{slash}SPI2_MOSI{slash}I2S2_SD{slash}TIM12_CH2{slash}OTG_HS_DP{slash}EVENTOUT-Pad36)") (class "Default")
      (node (ref "U6") (pin "36") (pinfunction "PB15/RTC_REFIN/TIM1_CH3N/TIM8_CH3N/SPI2_MOSI/I2S2_SD/TIM12_CH2/OTG_HS_DP/EVENTOUT_36") (pintype "bidirectional"))
    )
    (net (code "177") (name "unconnected-(U6-PC0{slash}SAI1_MCLK_B{slash}OTG_HS_ULPI_STP{slash}FMC_SDNWE{slash}EVENTOUT-Pad8)") (class "Default")
      (node (ref "U6") (pin "8") (pinfunction "PC0/SAI1_MCLK_B/OTG_HS_ULPI_STP/FMC_SDNWE/EVENTOUT_8") (pintype "bidirectional"))
    )
    (net (code "178") (name "unconnected-(U6-PC1{slash}SPI3_MOSI{slash}I2S3_SD{slash}SAI1_SD_A{slash}SPI2_MOSI{slash}I2S2_SD{slash}EVENTOUT-Pad9)") (class "Default")
      (node (ref "U6") (pin "9") (pinfunction "PC1/SPI3_MOSI/I2S3_SD/SAI1_SD_A/SPI2_MOSI/I2S2_SD/EVENTOUT_9") (pintype "bidirectional"))
    )
    (net (code "179") (name "unconnected-(U6-PC2{slash}SPI2_MISO{slash}OTG_HS_ULPI_DIR{slash}FMC_SDNE0{slash}EVENTOUT-Pad10)") (class "Default")
      (node (ref "U6") (pin "10") (pinfunction "PC2/SPI2_MISO/OTG_HS_ULPI_DIR/FMC_SDNE0/EVENTOUT_10") (pintype "bidirectional"))
    )
    (net (code "180") (name "unconnected-(U6-PC3{slash}SPI2_MOSI{slash}I2S2_SD{slash}OTG_HS_ULPI_NXT{slash}FMC_SDCKE0{slash}EVENTOUT-Pad11)") (class "Default")
      (node (ref "U6") (pin "11") (pinfunction "PC3/SPI2_MOSI/I2S2_SD/OTG_HS_ULPI_NXT/FMC_SDCKE0/EVENTOUT_11") (pintype "bidirectional"))
    )
    (net (code "181") (name "unconnected-(U6-PC4{slash}I2S1_MCK{slash}SPDIFRX_IN2{slash}FMC_SDNE0{slash}EVENTOUT-Pad24)") (class "Default")
      (node (ref "U6") (pin "24") (pinfunction "PC4/I2S1_MCK/SPDIFRX_IN2/FMC_SDNE0/EVENTOUT_24") (pintype "bidirectional"))
    )
    (net (code "182") (name "unconnected-(U6-PC5{slash}USART3_RX{slash}SPDIFRX_IN3{slash}FMC_SDCKE0{slash}EVENTOUT-Pad25)") (class "Default")
      (node (ref "U6") (pin "25") (pinfunction "PC5/USART3_RX/SPDIFRX_IN3/FMC_SDCKE0/EVENTOUT_25") (pintype "bidirectional"))
    )
    (net (code "183") (name "unconnected-(U6-PC8{slash}TRACED0{slash}TIM3_CH3{slash}TIM8_CH3{slash}UART5_RTS{slash}USART6_CK{slash}SDIO_D0{slash}DCMI_D2{slash}EVENTOUT-Pad39)") (class "Default")
      (node (ref "U6") (pin "39") (pinfunction "PC8/TRACED0/TIM3_CH3/TIM8_CH3/UART5_RTS/USART6_CK/SDIO_D0/DCMI_D2/EVENTOUT_39") (pintype "bidirectional"))
    )
    (net (code "184") (name "unconnected-(U6-PC9{slash}MCO2{slash}TIM3_CH4{slash}TIM8_CH4{slash}I2C3_SDA{slash}I2S_CKIN{slash}UART5_CTS{slash}QUADSPI_BK1_IO0{slash}SDIO_D1{slash}DCMI_D3{slash}EVENTOUT-Pad40)") (class "Default")
      (node (ref "U6") (pin "40") (pinfunction "PC9/MCO2/TIM3_CH4/TIM8_CH4/I2C3_SDA/I2S_CKIN/UART5_CTS/QUADSPI_BK1_IO0/SDIO_D1/DCMI_D3/EVENTOUT_40") (pintype "bidirectional"))
    )
    (net (code "185") (name "unconnected-(U6-PC10{slash}SPI3_SCK{slash}I2S3_CK{slash}USART3_TX{slash}UART4_TX{slash}QUADSPI_BK1_IO1{slash}SDIO_D2{slash}DCMI_D8{slash}EVENTOUT-Pad51)") (class "Default")
      (node (ref "U6") (pin "51") (pinfunction "PC10/SPI3_SCK/I2S3_CK/USART3_TX/UART4_TX/QUADSPI_BK1_IO1/SDIO_D2/DCMI_D8/EVENTOUT_51") (pintype "bidirectional"))
    )
    (net (code "186") (name "unconnected-(U6-PC11{slash}SPI3_MISO{slash}USART3_RX{slash}UART4_RX{slash}QUADSPI_BK2_NCS{slash}SDIO_D3{slash}DCMI_D4{slash}EVENTOUT-Pad52)") (class "Default")
      (node (ref "U6") (pin "52") (pinfunction "PC11/SPI3_MISO/USART3_RX/UART4_RX/QUADSPI_BK2_NCS/SDIO_D3/DCMI_D4/EVENTOUT_52") (pintype "bidirectional"))
    )
    (net (code "187") (name "unconnected-(U6-PC13{slash}EVENTOUT-Pad2)") (class "Default")
      (node (ref "U6") (pin "2") (pinfunction "PC13/EVENTOUT_2") (pintype "bidirectional"))
    )
    (net (code "188") (name "unconnected-(U6-PC14-OSC32_IN(PC14){slash}EVENTOUT-Pad3)") (class "Default")
      (node (ref "U6") (pin "3") (pinfunction "PC14-OSC32_IN(PC14)/EVENTOUT_3") (pintype "bidirectional"))
    )
    (net (code "189") (name "unconnected-(U6-PC15-OSC32_OUT(PC15){slash}EVENTOUT-Pad4)") (class "Default")
      (node (ref "U6") (pin "4") (pinfunction "PC15-OSC32_OUT(PC15)/EVENTOUT_4") (pintype "bidirectional"))
    )
  )
)
